# SCH_Hacker-Card_2025-02-01.net
KiCad netlist of a schematic drawn in EasyEDA
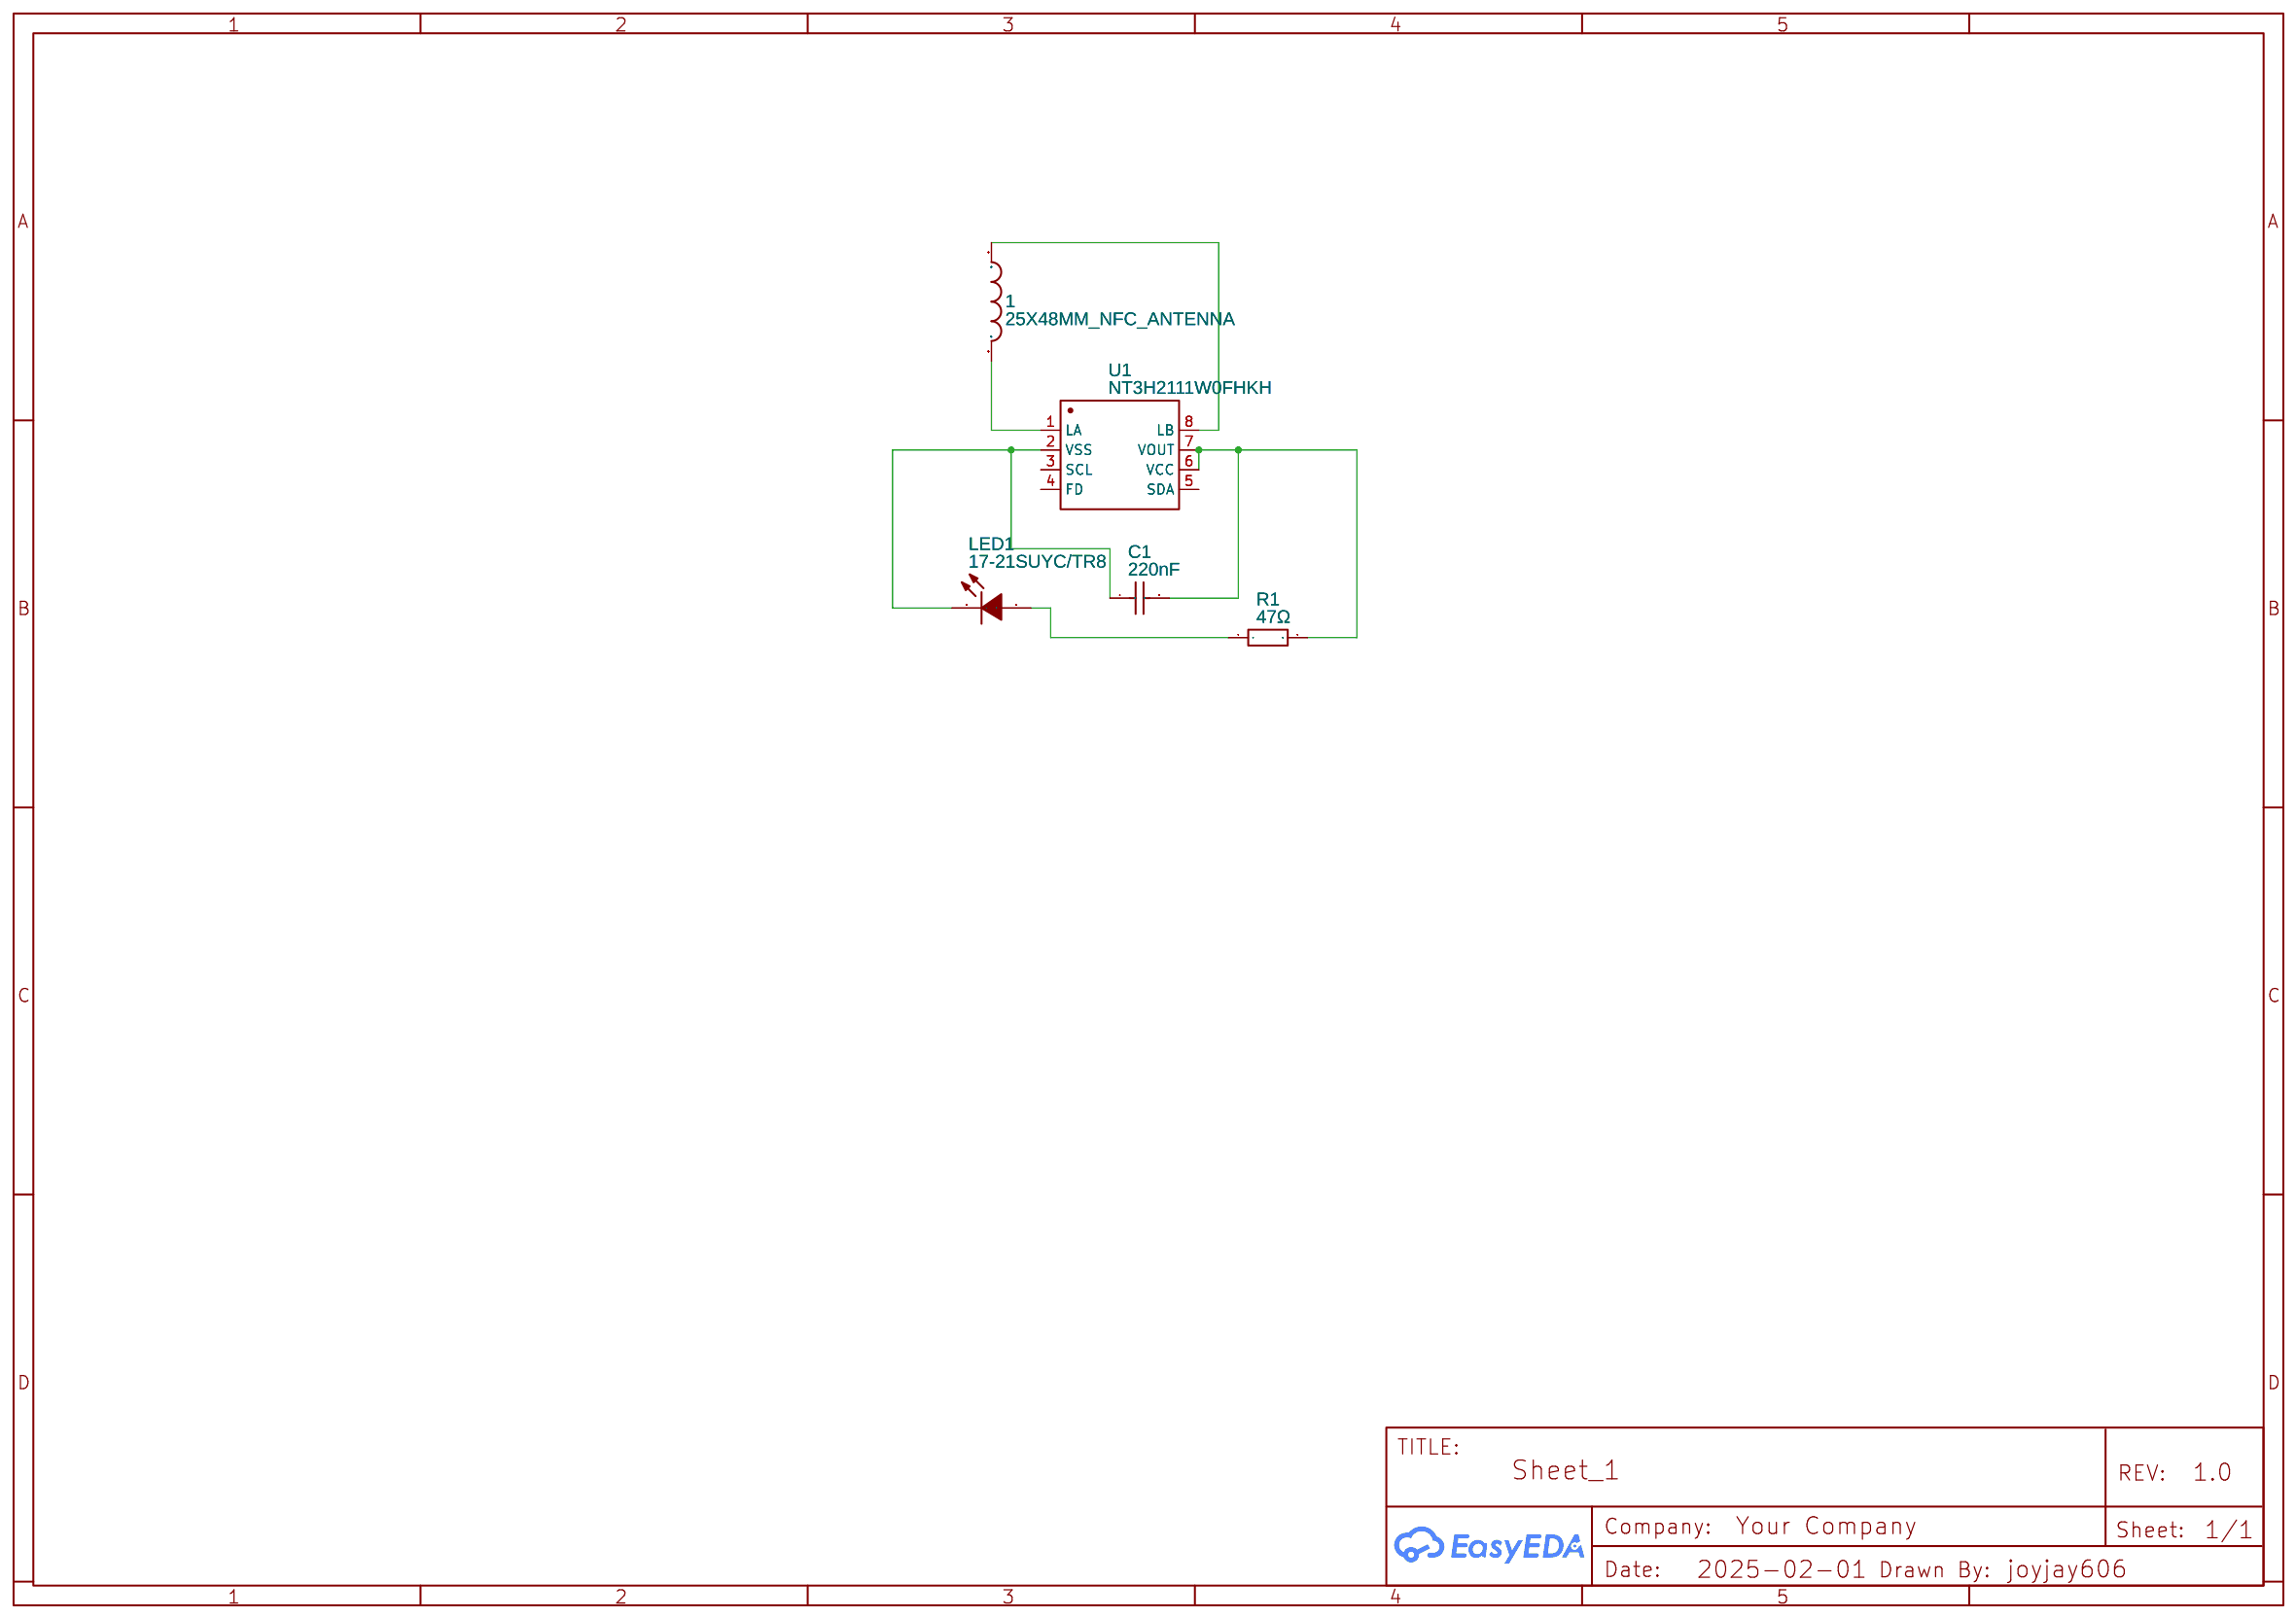
[diagram p0: schematic sheet]

(export (version "E")
  (design (tool "Eeschema 10.0.6"))
  (components
    (comp (ref "1") (value "25X48MM_NFC_ANTENNA") (libsource (lib "") (part "25X48MM_NFC_ANTENNA")))
    (comp (ref "C1")
      (value "220nF")
      (fields
        (field (name "Manufacturer Part") "CL10B224KA8NNNC")
        (field (name "Manufacturer") "SAMSUNG(三星)")
      )
      (libsource (lib "") (part "CL10B224KA8NNNC"))
    )
    (comp (ref "LED1")
      (value "17-21SUYC/TR8")
      (fields (field (name "Manufacturer Part") "KT-0805黄灯") (field (name "Manufacturer") "KENTO"))
      (libsource (lib "") (part "17-21SUYC/TR8"))
    )
    (comp (ref "R1")
      (value "47Ω")
      (fields
        (field (name "Manufacturer Part") "0603WAF470JT5E")
        (field (name "Manufacturer") "UNI-ROYAL(厚声)")
      )
      (libsource (lib "") (part "0603WAF470JT5E"))
    )
    (comp (ref "U1")
      (value "NT3H2111W0FHKH")
      (fields (field (name "Manufacturer") "NXP(恩智浦)"))
      (libsource (lib "") (part "NT3H2111W0FHKH"))
    )
  )
  (nets
    (net (code "1") (name "Net-(LED1-+)") (class "Default")
      (node (ref "LED1") (pin "1") (pinfunction "+_1") (pintype "unspecified"))
      (node (ref "R1") (pin "1") (pinfunction "1_1") (pintype "input"))
    )
    (net (code "2") (name "Net-(LED1--)") (class "Default")
      (node (ref "C1") (pin "1") (pinfunction "1_1") (pintype "input"))
      (node (ref "LED1") (pin "2") (pinfunction "-_2") (pintype "unspecified"))
      (node (ref "U1") (pin "2") (pinfunction "VSS_2") (pintype "unspecified"))
    )
    (net (code "3") (name "Net-(U1-LA)") (class "Default")
      (node (ref "1") (pin "P$2") (pinfunction "P$2_P$2") (pintype "bidirectional"))
      (node (ref "U1") (pin "1") (pinfunction "LA_1") (pintype "unspecified"))
    )
    (net (code "4") (name "Net-(U1-LB)") (class "Default")
      (node (ref "1") (pin "P$1") (pinfunction "P$1_P$1") (pintype "bidirectional"))
      (node (ref "U1") (pin "8") (pinfunction "LB_8") (pintype "unspecified"))
    )
    (net (code "5") (name "Net-(U1-VCC)") (class "Default")
      (node (ref "C1") (pin "2") (pinfunction "2_2") (pintype "input"))
      (node (ref "R1") (pin "2") (pinfunction "2_2") (pintype "input"))
      (node (ref "U1") (pin "6") (pinfunction "VCC_6") (pintype "unspecified"))
      (node (ref "U1") (pin "7") (pinfunction "VOUT_7") (pintype "unspecified"))
    )
    (net (code "6") (name "unconnected-(U1-FD-Pad4)") (class "Default")
      (node (ref "U1") (pin "4") (pinfunction "FD_4") (pintype "unspecified"))
    )
    (net (code "7") (name "unconnected-(U1-SCL-Pad3)") (class "Default")
      (node (ref "U1") (pin "3") (pinfunction "SCL_3") (pintype "unspecified"))
    )
    (net (code "8") (name "unconnected-(U1-SDA-Pad5)") (class "Default")
      (node (ref "U1") (pin "5") (pinfunction "SDA_5") (pintype "unspecified"))
    )
  )
)
